# Schematic.net
KiCad netlist of a schematic drawn in Altium Designer
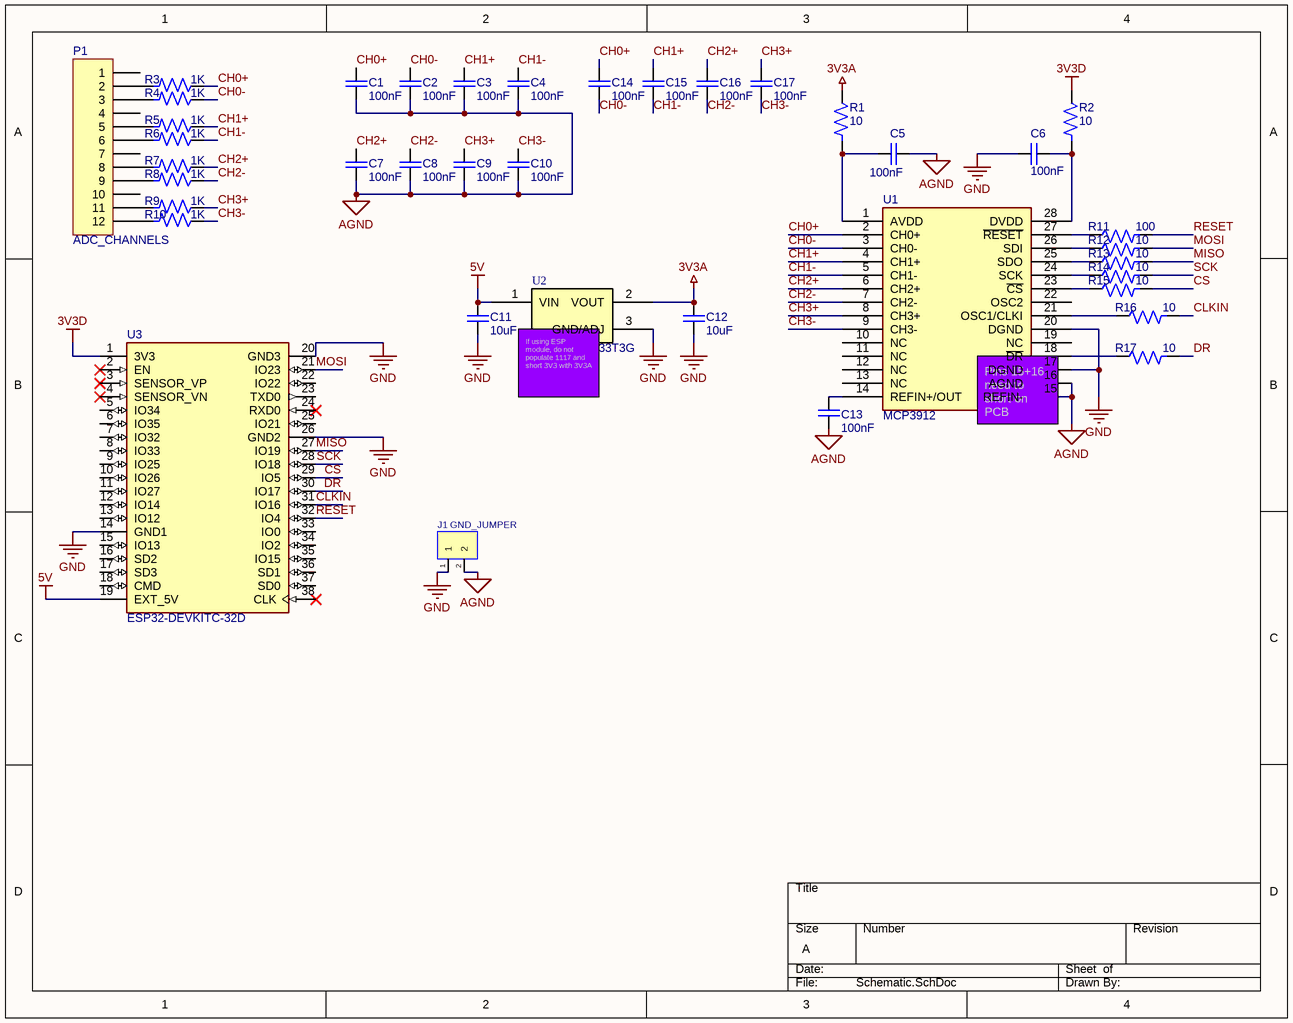
[diagram p0: Schematic.SchDoc]

(export (version "E")
  (design (tool "Eeschema 10.0.6"))
  (components
    (comp (ref "C1")
      (value "100nF")
      (footprint "CAP_0603")
      (description "Cap 100nF 6V 603 Ceramic")
      (fields
        (field (name "MANUFACTURER") "KEMET")
        (field (name "MANUFACTURER PART NUMBER") "C0603C104K9RACTU")
      )
      (libsource (lib "collection1") (part "Cap 100nF 6V 603 Ceramic"))
    )
    (comp (ref "C2")
      (value "100nF")
      (footprint "CAP_0603")
      (description "Cap 100nF 6V 603 Ceramic")
      (fields
        (field (name "MANUFACTURER") "KEMET")
        (field (name "MANUFACTURER PART NUMBER") "C0603C104K9RACTU")
      )
      (libsource (lib "collection1") (part "Cap 100nF 6V 603 Ceramic"))
    )
    (comp (ref "C3")
      (value "100nF")
      (footprint "CAP_0603")
      (description "Cap 100nF 6V 603 Ceramic")
      (fields
        (field (name "MANUFACTURER") "KEMET")
        (field (name "MANUFACTURER PART NUMBER") "C0603C104K9RACTU")
      )
      (libsource (lib "collection1") (part "Cap 100nF 6V 603 Ceramic"))
    )
    (comp (ref "C4")
      (value "100nF")
      (footprint "CAP_0603")
      (description "Cap 100nF 6V 603 Ceramic")
      (fields
        (field (name "MANUFACTURER") "KEMET")
        (field (name "MANUFACTURER PART NUMBER") "C0603C104K9RACTU")
      )
      (libsource (lib "collection1") (part "Cap 100nF 6V 603 Ceramic"))
    )
    (comp (ref "C5")
      (value "100nF")
      (footprint "CAP_0603")
      (description "Cap 100nF 6V 603 Ceramic")
      (fields
        (field (name "MANUFACTURER") "KEMET")
        (field (name "MANUFACTURER PART NUMBER") "C0603C104K9RACTU")
      )
      (libsource (lib "collection1") (part "Cap 100nF 6V 603 Ceramic"))
    )
    (comp (ref "C6")
      (value "100nF")
      (footprint "CAP_0603")
      (description "Cap 100nF 6V 603 Ceramic")
      (fields
        (field (name "MANUFACTURER") "KEMET")
        (field (name "MANUFACTURER PART NUMBER") "C0603C104K9RACTU")
      )
      (libsource (lib "collection1") (part "Cap 100nF 6V 603 Ceramic"))
    )
    (comp (ref "C7")
      (value "100nF")
      (footprint "CAP_0603")
      (description "Cap 100nF 6V 603 Ceramic")
      (fields
        (field (name "MANUFACTURER") "KEMET")
        (field (name "MANUFACTURER PART NUMBER") "C0603C104K9RACTU")
      )
      (libsource (lib "collection1") (part "Cap 100nF 6V 603 Ceramic"))
    )
    (comp (ref "C8")
      (value "100nF")
      (footprint "CAP_0603")
      (description "Cap 100nF 6V 603 Ceramic")
      (fields
        (field (name "MANUFACTURER") "KEMET")
        (field (name "MANUFACTURER PART NUMBER") "C0603C104K9RACTU")
      )
      (libsource (lib "collection1") (part "Cap 100nF 6V 603 Ceramic"))
    )
    (comp (ref "C9")
      (value "100nF")
      (footprint "CAP_0603")
      (description "Cap 100nF 6V 603 Ceramic")
      (fields
        (field (name "MANUFACTURER") "KEMET")
        (field (name "MANUFACTURER PART NUMBER") "C0603C104K9RACTU")
      )
      (libsource (lib "collection1") (part "Cap 100nF 6V 603 Ceramic"))
    )
    (comp (ref "C10")
      (value "100nF")
      (footprint "CAP_0603")
      (description "Cap 100nF 6V 603 Ceramic")
      (fields
        (field (name "MANUFACTURER") "KEMET")
        (field (name "MANUFACTURER PART NUMBER") "C0603C104K9RACTU")
      )
      (libsource (lib "collection1") (part "Cap 100nF 6V 603 Ceramic"))
    )
    (comp (ref "C11")
      (value "10uF")
      (footprint "CAP_0603")
      (description "Cap 100nF 6V 603 Ceramic")
      (fields
        (field (name "MANUFACTURER") "KEMET")
        (field (name "MANUFACTURER PART NUMBER") "C0603C104K9RACTU")
      )
      (libsource (lib "collection1") (part "Cap 100nF 6V 603 Ceramic"))
    )
    (comp (ref "C12")
      (value "10uF")
      (footprint "CAP_0603")
      (description "Cap 100nF 6V 603 Ceramic")
      (fields
        (field (name "MANUFACTURER") "KEMET")
        (field (name "MANUFACTURER PART NUMBER") "C0603C104K9RACTU")
      )
      (libsource (lib "collection1") (part "Cap 100nF 6V 603 Ceramic"))
    )
    (comp (ref "C13")
      (value "100nF")
      (footprint "CAP_0603")
      (description "Cap 100nF 6V 603 Ceramic")
      (fields
        (field (name "MANUFACTURER") "KEMET")
        (field (name "MANUFACTURER PART NUMBER") "C0603C104K9RACTU")
      )
      (libsource (lib "collection1") (part "Cap 100nF 6V 603 Ceramic"))
    )
    (comp (ref "C14")
      (value "100nF")
      (footprint "CAP_0603")
      (description "Cap 100nF 6V 603 Ceramic")
      (fields
        (field (name "MANUFACTURER") "KEMET")
        (field (name "MANUFACTURER PART NUMBER") "C0603C104K9RACTU")
      )
      (libsource (lib "collection1") (part "Cap 100nF 6V 603 Ceramic"))
    )
    (comp (ref "C15")
      (value "100nF")
      (footprint "CAP_0603")
      (description "Cap 100nF 6V 603 Ceramic")
      (fields
        (field (name "MANUFACTURER") "KEMET")
        (field (name "MANUFACTURER PART NUMBER") "C0603C104K9RACTU")
      )
      (libsource (lib "collection1") (part "Cap 100nF 6V 603 Ceramic"))
    )
    (comp (ref "C16")
      (value "100nF")
      (footprint "CAP_0603")
      (description "Cap 100nF 6V 603 Ceramic")
      (fields
        (field (name "MANUFACTURER") "KEMET")
        (field (name "MANUFACTURER PART NUMBER") "C0603C104K9RACTU")
      )
      (libsource (lib "collection1") (part "Cap 100nF 6V 603 Ceramic"))
    )
    (comp (ref "C17")
      (value "100nF")
      (footprint "CAP_0603")
      (description "Cap 100nF 6V 603 Ceramic")
      (fields
        (field (name "MANUFACTURER") "KEMET")
        (field (name "MANUFACTURER PART NUMBER") "C0603C104K9RACTU")
      )
      (libsource (lib "collection1") (part "Cap 100nF 6V 603 Ceramic"))
    )
    (comp (ref "J1")
      (value "GND_JUMPER")
      (footprint "CONN 2POS 2.54PITCH")
      (description "Connector Header Through Hole 2 position 0.100\" (2.54mm)")
      (fields (field (name "MANUFACTURER") "Molex") (field (name "MANUFACTURER PART NUMBER") "22-27-2021"))
      (libsource (lib "collection1") (part "CONN HEADER VERT 2POS 2.54MM"))
    )
    (comp (ref "P1")
      (value "ADC_CHANNELS")
      (footprint "HDR1X12")
      (description "Header, 12-Pin")
      (fields (field (name "PUBLISHER") "Altium Limited"))
      (libsource (lib "Miscellaneous Connectors") (part "Header 12"))
    )
    (comp (ref "R1")
      (value "10")
      (footprint "RES_0805")
      (description "Res 1K 0805 5% 1/8W")
      (fields
        (field (name "MANUFACTURER") "Yageo")
        (field (name "MANUFACTURER PART NUMBER") "RC0805JR-071KL")
      )
      (libsource (lib "collection1") (part "Res 1K 0805 5% 1/8W"))
    )
    (comp (ref "R2")
      (value "10")
      (footprint "RES_0805")
      (description "Res 1K 0805 5% 1/8W")
      (fields
        (field (name "MANUFACTURER") "Yageo")
        (field (name "MANUFACTURER PART NUMBER") "RC0805JR-071KL")
      )
      (libsource (lib "collection1") (part "Res 1K 0805 5% 1/8W"))
    )
    (comp (ref "R3")
      (value "1K")
      (footprint "RES_0805")
      (description "Res 1K 0805 5% 1/8W")
      (fields
        (field (name "MANUFACTURER") "Yageo")
        (field (name "MANUFACTURER PART NUMBER") "RC0805JR-071KL")
      )
      (libsource (lib "collection1") (part "Res 1K 0805 5% 1/8W"))
    )
    (comp (ref "R4")
      (value "1K")
      (footprint "RES_0805")
      (description "Res 1K 0805 5% 1/8W")
      (fields
        (field (name "MANUFACTURER") "Yageo")
        (field (name "MANUFACTURER PART NUMBER") "RC0805JR-071KL")
      )
      (libsource (lib "collection1") (part "Res 1K 0805 5% 1/8W"))
    )
    (comp (ref "R5")
      (value "1K")
      (footprint "RES_0805")
      (description "Res 1K 0805 5% 1/8W")
      (fields
        (field (name "MANUFACTURER") "Yageo")
        (field (name "MANUFACTURER PART NUMBER") "RC0805JR-071KL")
      )
      (libsource (lib "collection1") (part "Res 1K 0805 5% 1/8W"))
    )
    (comp (ref "R6")
      (value "1K")
      (footprint "RES_0805")
      (description "Res 1K 0805 5% 1/8W")
      (fields
        (field (name "MANUFACTURER") "Yageo")
        (field (name "MANUFACTURER PART NUMBER") "RC0805JR-071KL")
      )
      (libsource (lib "collection1") (part "Res 1K 0805 5% 1/8W"))
    )
    (comp (ref "R7")
      (value "1K")
      (footprint "RES_0805")
      (description "Res 1K 0805 5% 1/8W")
      (fields
        (field (name "MANUFACTURER") "Yageo")
        (field (name "MANUFACTURER PART NUMBER") "RC0805JR-071KL")
      )
      (libsource (lib "collection1") (part "Res 1K 0805 5% 1/8W"))
    )
    (comp (ref "R8")
      (value "1K")
      (footprint "RES_0805")
      (description "Res 1K 0805 5% 1/8W")
      (fields
        (field (name "MANUFACTURER") "Yageo")
        (field (name "MANUFACTURER PART NUMBER") "RC0805JR-071KL")
      )
      (libsource (lib "collection1") (part "Res 1K 0805 5% 1/8W"))
    )
    (comp (ref "R9")
      (value "1K")
      (footprint "RES_0805")
      (description "Res 1K 0805 5% 1/8W")
      (fields
        (field (name "MANUFACTURER") "Yageo")
        (field (name "MANUFACTURER PART NUMBER") "RC0805JR-071KL")
      )
      (libsource (lib "collection1") (part "Res 1K 0805 5% 1/8W"))
    )
    (comp (ref "R10")
      (value "1K")
      (footprint "RES_0805")
      (description "Res 1K 0805 5% 1/8W")
      (fields
        (field (name "MANUFACTURER") "Yageo")
        (field (name "MANUFACTURER PART NUMBER") "RC0805JR-071KL")
      )
      (libsource (lib "collection1") (part "Res 1K 0805 5% 1/8W"))
    )
    (comp (ref "R11")
      (value "100")
      (footprint "RES_0805")
      (description "Res 1K 0805 5% 1/8W")
      (fields
        (field (name "MANUFACTURER") "Yageo")
        (field (name "MANUFACTURER PART NUMBER") "RC0805JR-071KL")
      )
      (libsource (lib "collection1") (part "Res 1K 0805 5% 1/8W"))
    )
    (comp (ref "R12")
      (value "10")
      (footprint "RES_0805")
      (description "Res 1K 0805 5% 1/8W")
      (fields
        (field (name "MANUFACTURER") "Yageo")
        (field (name "MANUFACTURER PART NUMBER") "RC0805JR-071KL")
      )
      (libsource (lib "collection1") (part "Res 1K 0805 5% 1/8W"))
    )
    (comp (ref "R13")
      (value "10")
      (footprint "RES_0805")
      (description "Res 1K 0805 5% 1/8W")
      (fields
        (field (name "MANUFACTURER") "Yageo")
        (field (name "MANUFACTURER PART NUMBER") "RC0805JR-071KL")
      )
      (libsource (lib "collection1") (part "Res 1K 0805 5% 1/8W"))
    )
    (comp (ref "R14")
      (value "10")
      (footprint "RES_0805")
      (description "Res 1K 0805 5% 1/8W")
      (fields
        (field (name "MANUFACTURER") "Yageo")
        (field (name "MANUFACTURER PART NUMBER") "RC0805JR-071KL")
      )
      (libsource (lib "collection1") (part "Res 1K 0805 5% 1/8W"))
    )
    (comp (ref "R15")
      (value "10")
      (footprint "RES_0805")
      (description "Res 1K 0805 5% 1/8W")
      (fields
        (field (name "MANUFACTURER") "Yageo")
        (field (name "MANUFACTURER PART NUMBER") "RC0805JR-071KL")
      )
      (libsource (lib "collection1") (part "Res 1K 0805 5% 1/8W"))
    )
    (comp (ref "R16")
      (value "10")
      (footprint "RES_0805")
      (description "Res 1K 0805 5% 1/8W")
      (fields
        (field (name "MANUFACTURER") "Yageo")
        (field (name "MANUFACTURER PART NUMBER") "RC0805JR-071KL")
      )
      (libsource (lib "collection1") (part "Res 1K 0805 5% 1/8W"))
    )
    (comp (ref "R17")
      (value "10")
      (footprint "RES_0805")
      (description "Res 1K 0805 5% 1/8W")
      (fields
        (field (name "MANUFACTURER") "Yageo")
        (field (name "MANUFACTURER PART NUMBER") "RC0805JR-071KL")
      )
      (libsource (lib "collection1") (part "Res 1K 0805 5% 1/8W"))
    )
    (comp (ref "U1")
      (value "MCP3912")
      (footprint "TI SSOP-24 DB")
      (libsource (lib "bio_components") (part "MCP3912"))
    )
    (comp (ref "U2")
      (value "NCP1117ST33T3G")
      (footprint "SOT223")
      (libsource (lib "ch340C") (part "NCP1117ST33T3G"))
    )
    (comp (ref "U3")
      (value "ESP32-DEVKITC-32D")
      (footprint "MODULE_ESP32-DEVKITC-32D:MODULE_ESP32-DEVKITC-32D")
      (description "EVAL BOARD FOR ESP-WROOM-32")
      (fields (field (name "MF") "Espressif Systems"))
      (libsource (lib "bio_components") (part "ESP32-DEVKITC-32D"))
    )
  )
  (nets
    (net (code "1") (name "/CH0+") (class "Default")
      (node (ref "C1") (pin "1") (pinfunction "1_1") (pintype "passive"))
      (node (ref "C14") (pin "1") (pinfunction "1_1") (pintype "passive"))
      (node (ref "R3") (pin "2") (pinfunction "2_2") (pintype "passive"))
      (node (ref "U1") (pin "2") (pinfunction "CH0+_2") (pintype "passive"))
    )
    (net (code "2") (name "/CH0-") (class "Default")
      (node (ref "C14") (pin "2") (pinfunction "2_2") (pintype "passive"))
      (node (ref "C2") (pin "1") (pinfunction "1_1") (pintype "passive"))
      (node (ref "R4") (pin "2") (pinfunction "2_2") (pintype "passive"))
      (node (ref "U1") (pin "3") (pinfunction "CH0-_3") (pintype "passive"))
    )
    (net (code "3") (name "/CH1+") (class "Default")
      (node (ref "C15") (pin "1") (pinfunction "1_1") (pintype "passive"))
      (node (ref "C3") (pin "1") (pinfunction "1_1") (pintype "passive"))
      (node (ref "R5") (pin "2") (pinfunction "2_2") (pintype "passive"))
      (node (ref "U1") (pin "4") (pinfunction "CH1+_4") (pintype "passive"))
    )
    (net (code "4") (name "/CH1-") (class "Default")
      (node (ref "C15") (pin "2") (pinfunction "2_2") (pintype "passive"))
      (node (ref "C4") (pin "1") (pinfunction "1_1") (pintype "passive"))
      (node (ref "R6") (pin "2") (pinfunction "2_2") (pintype "passive"))
      (node (ref "U1") (pin "5") (pinfunction "CH1-_5") (pintype "passive"))
    )
    (net (code "5") (name "/CH2+") (class "Default")
      (node (ref "C16") (pin "1") (pinfunction "1_1") (pintype "passive"))
      (node (ref "C7") (pin "1") (pinfunction "1_1") (pintype "passive"))
      (node (ref "R7") (pin "2") (pinfunction "2_2") (pintype "passive"))
      (node (ref "U1") (pin "6") (pinfunction "CH2+_6") (pintype "passive"))
    )
    (net (code "6") (name "/CH2-") (class "Default")
      (node (ref "C16") (pin "2") (pinfunction "2_2") (pintype "passive"))
      (node (ref "C8") (pin "1") (pinfunction "1_1") (pintype "passive"))
      (node (ref "R8") (pin "2") (pinfunction "2_2") (pintype "passive"))
      (node (ref "U1") (pin "7") (pinfunction "CH2-_7") (pintype "passive"))
    )
    (net (code "7") (name "/CH3+") (class "Default")
      (node (ref "C17") (pin "1") (pinfunction "1_1") (pintype "passive"))
      (node (ref "C9") (pin "1") (pinfunction "1_1") (pintype "passive"))
      (node (ref "R9") (pin "2") (pinfunction "2_2") (pintype "passive"))
      (node (ref "U1") (pin "8") (pinfunction "CH3+_8") (pintype "passive"))
    )
    (net (code "8") (name "/CH3-") (class "Default")
      (node (ref "C10") (pin "1") (pinfunction "1_1") (pintype "passive"))
      (node (ref "C17") (pin "2") (pinfunction "2_2") (pintype "passive"))
      (node (ref "R10") (pin "2") (pinfunction "2_2") (pintype "passive"))
      (node (ref "U1") (pin "9") (pinfunction "CH3-_9") (pintype "passive"))
    )
    (net (code "9") (name "/CLKIN") (class "Default")
      (node (ref "R16") (pin "1") (pinfunction "1_1") (pintype "passive"))
      (node (ref "U3") (pin "31") (pinfunction "IO16_31") (pintype "bidirectional"))
    )
    (net (code "10") (name "/CS") (class "Default")
      (node (ref "R15") (pin "1") (pinfunction "1_1") (pintype "passive"))
      (node (ref "U3") (pin "29") (pinfunction "IO5_29") (pintype "bidirectional"))
    )
    (net (code "11") (name "/DR") (class "Default")
      (node (ref "R17") (pin "1") (pinfunction "1_1") (pintype "passive"))
      (node (ref "U3") (pin "30") (pinfunction "IO17_30") (pintype "bidirectional"))
    )
    (net (code "12") (name "/MISO") (class "Default")
      (node (ref "R13") (pin "1") (pinfunction "1_1") (pintype "passive"))
      (node (ref "U3") (pin "27") (pinfunction "IO19_27") (pintype "bidirectional"))
    )
    (net (code "13") (name "/MOSI") (class "Default")
      (node (ref "R12") (pin "1") (pinfunction "1_1") (pintype "passive"))
      (node (ref "U3") (pin "21") (pinfunction "IO23_21") (pintype "bidirectional"))
    )
    (net (code "14") (name "/RESET") (class "Default")
      (node (ref "R11") (pin "1") (pinfunction "1_1") (pintype "passive"))
      (node (ref "U3") (pin "32") (pinfunction "IO4_32") (pintype "bidirectional"))
    )
    (net (code "15") (name "/SCK") (class "Default")
      (node (ref "R14") (pin "1") (pinfunction "1_1") (pintype "passive"))
      (node (ref "U3") (pin "28") (pinfunction "IO18_28") (pintype "bidirectional"))
    )
    (net (code "16") (name "3V3A") (class "Default")
      (node (ref "C12") (pin "1") (pinfunction "1_1") (pintype "passive"))
      (node (ref "R1") (pin "2") (pinfunction "2_2") (pintype "passive"))
      (node (ref "U2") (pin "2") (pinfunction "VOUT_2") (pintype "passive"))
    )
    (net (code "17") (name "3V3D") (class "Default")
      (node (ref "R2") (pin "2") (pinfunction "2_2") (pintype "passive"))
      (node (ref "U3") (pin "1") (pinfunction "3V3_1") (pintype "power_in"))
    )
    (net (code "18") (name "5V") (class "Default")
      (node (ref "C11") (pin "1") (pinfunction "1_1") (pintype "passive"))
      (node (ref "U2") (pin "1") (pinfunction "VIN_1") (pintype "passive"))
      (node (ref "U3") (pin "19") (pinfunction "EXT_5V_19") (pintype "power_in"))
    )
    (net (code "19") (name "AGND") (class "Default")
      (node (ref "C1") (pin "2") (pinfunction "2_2") (pintype "passive"))
      (node (ref "C10") (pin "2") (pinfunction "2_2") (pintype "passive"))
      (node (ref "C13") (pin "1") (pinfunction "1_1") (pintype "passive"))
      (node (ref "C2") (pin "2") (pinfunction "2_2") (pintype "passive"))
      (node (ref "C3") (pin "2") (pinfunction "2_2") (pintype "passive"))
      (node (ref "C4") (pin "2") (pinfunction "2_2") (pintype "passive"))
      (node (ref "C5") (pin "2") (pinfunction "2_2") (pintype "passive"))
      (node (ref "C7") (pin "2") (pinfunction "2_2") (pintype "passive"))
      (node (ref "C8") (pin "2") (pinfunction "2_2") (pintype "passive"))
      (node (ref "C9") (pin "2") (pinfunction "2_2") (pintype "passive"))
      (node (ref "J1") (pin "2") (pinfunction "2_2") (pintype "passive"))
      (node (ref "U1") (pin "15") (pinfunction "REFIN-_15") (pintype "passive"))
      (node (ref "U1") (pin "16") (pinfunction "AGND_16") (pintype "passive"))
    )
    (net (code "20") (name "GND") (class "Default")
      (node (ref "C11") (pin "2") (pinfunction "2_2") (pintype "passive"))
      (node (ref "C12") (pin "2") (pinfunction "2_2") (pintype "passive"))
      (node (ref "C6") (pin "1") (pinfunction "1_1") (pintype "passive"))
      (node (ref "J1") (pin "1") (pinfunction "1_1") (pintype "passive"))
      (node (ref "U1") (pin "17") (pinfunction "DGND_17") (pintype "passive"))
      (node (ref "U1") (pin "20") (pinfunction "DGND_20") (pintype "passive"))
      (node (ref "U2") (pin "3") (pinfunction "GND/ADJ_3") (pintype "passive"))
      (node (ref "U3") (pin "14") (pinfunction "GND1_14") (pintype "power_in"))
      (node (ref "U3") (pin "20") (pinfunction "GND3_20") (pintype "power_in"))
      (node (ref "U3") (pin "26") (pinfunction "GND2_26") (pintype "power_in"))
    )
    (net (code "21") (name "Net-(P1-Pad2)") (class "Default")
      (node (ref "P1") (pin "2") (pinfunction "2_2") (pintype "passive"))
      (node (ref "R3") (pin "1") (pinfunction "1_1") (pintype "passive"))
    )
    (net (code "22") (name "Net-(P1-Pad3)") (class "Default")
      (node (ref "P1") (pin "3") (pinfunction "3_3") (pintype "passive"))
      (node (ref "R4") (pin "1") (pinfunction "1_1") (pintype "passive"))
    )
    (net (code "23") (name "Net-(P1-Pad5)") (class "Default")
      (node (ref "P1") (pin "5") (pinfunction "5_5") (pintype "passive"))
      (node (ref "R5") (pin "1") (pinfunction "1_1") (pintype "passive"))
    )
    (net (code "24") (name "Net-(P1-Pad6)") (class "Default")
      (node (ref "P1") (pin "6") (pinfunction "6_6") (pintype "passive"))
      (node (ref "R6") (pin "1") (pinfunction "1_1") (pintype "passive"))
    )
    (net (code "25") (name "Net-(P1-Pad8)") (class "Default")
      (node (ref "P1") (pin "8") (pinfunction "8_8") (pintype "passive"))
      (node (ref "R7") (pin "1") (pinfunction "1_1") (pintype "passive"))
    )
    (net (code "26") (name "Net-(P1-Pad9)") (class "Default")
      (node (ref "P1") (pin "9") (pinfunction "9_9") (pintype "passive"))
      (node (ref "R8") (pin "1") (pinfunction "1_1") (pintype "passive"))
    )
    (net (code "27") (name "Net-(P1-Pad11)") (class "Default")
      (node (ref "P1") (pin "11") (pinfunction "11_11") (pintype "passive"))
      (node (ref "R9") (pin "1") (pinfunction "1_1") (pintype "passive"))
    )
    (net (code "28") (name "Net-(P1-Pad12)") (class "Default")
      (node (ref "P1") (pin "12") (pinfunction "12_12") (pintype "passive"))
      (node (ref "R10") (pin "1") (pinfunction "1_1") (pintype "passive"))
    )
    (net (code "29") (name "Net-(U1-AVDD)") (class "Default")
      (node (ref "C5") (pin "1") (pinfunction "1_1") (pintype "passive"))
      (node (ref "R1") (pin "1") (pinfunction "1_1") (pintype "passive"))
      (node (ref "U1") (pin "1") (pinfunction "AVDD_1") (pintype "passive"))
    )
    (net (code "30") (name "Net-(U1-DVDD)") (class "Default")
      (node (ref "C6") (pin "2") (pinfunction "2_2") (pintype "passive"))
      (node (ref "R2") (pin "1") (pinfunction "1_1") (pintype "passive"))
      (node (ref "U1") (pin "28") (pinfunction "DVDD_28") (pintype "passive"))
    )
    (net (code "31") (name "Net-(U1-OSC1{slash}CLKI)") (class "Default")
      (node (ref "R16") (pin "2") (pinfunction "2_2") (pintype "passive"))
      (node (ref "U1") (pin "21") (pinfunction "OSC1/CLKI_21") (pintype "passive"))
    )
    (net (code "32") (name "Net-(U1-REFIN+{slash}OUT)") (class "Default")
      (node (ref "C13") (pin "2") (pinfunction "2_2") (pintype "passive"))
      (node (ref "U1") (pin "14") (pinfunction "REFIN+/OUT_14") (pintype "passive"))
    )
    (net (code "33") (name "Net-(U1-SCK)") (class "Default")
      (node (ref "R14") (pin "2") (pinfunction "2_2") (pintype "passive"))
      (node (ref "U1") (pin "24") (pinfunction "SCK_24") (pintype "passive"))
    )
    (net (code "34") (name "Net-(U1-SDI)") (class "Default")
      (node (ref "R12") (pin "2") (pinfunction "2_2") (pintype "passive"))
      (node (ref "U1") (pin "26") (pinfunction "SDI_26") (pintype "passive"))
    )
    (net (code "35") (name "Net-(U1-SDO)") (class "Default")
      (node (ref "R13") (pin "2") (pinfunction "2_2") (pintype "passive"))
      (node (ref "U1") (pin "25") (pinfunction "SDO_25") (pintype "passive"))
    )
    (net (code "36") (name "Net-(U1-~{CS})") (class "Default")
      (node (ref "R15") (pin "2") (pinfunction "2_2") (pintype "passive"))
      (node (ref "U1") (pin "23") (pinfunction "~{CS}_23") (pintype "passive"))
    )
    (net (code "37") (name "Net-(U1-~{DR})") (class "Default")
      (node (ref "R17") (pin "2") (pinfunction "2_2") (pintype "passive"))
      (node (ref "U1") (pin "18") (pinfunction "~{DR}_18") (pintype "passive"))
    )
    (net (code "38") (name "Net-(U1-~{RESET})") (class "Default")
      (node (ref "R11") (pin "2") (pinfunction "2_2") (pintype "passive"))
      (node (ref "U1") (pin "27") (pinfunction "~{RESET}_27") (pintype "passive"))
    )
    (net (code "39") (name "unconnected-(P1-Pad1)") (class "Default")
      (node (ref "P1") (pin "1") (pinfunction "1_1") (pintype "passive"))
    )
    (net (code "40") (name "unconnected-(P1-Pad4)") (class "Default")
      (node (ref "P1") (pin "4") (pinfunction "4_4") (pintype "passive"))
    )
    (net (code "41") (name "unconnected-(P1-Pad7)") (class "Default")
      (node (ref "P1") (pin "7") (pinfunction "7_7") (pintype "passive"))
    )
    (net (code "42") (name "unconnected-(P1-Pad10)") (class "Default")
      (node (ref "P1") (pin "10") (pinfunction "10_10") (pintype "passive"))
    )
    (net (code "43") (name "unconnected-(U1-NC-Pad10)") (class "Default")
      (node (ref "U1") (pin "10") (pinfunction "NC_10") (pintype "passive"))
    )
    (net (code "44") (name "unconnected-(U1-NC-Pad11)") (class "Default")
      (node (ref "U1") (pin "11") (pinfunction "NC_11") (pintype "passive"))
    )
    (net (code "45") (name "unconnected-(U1-NC-Pad12)") (class "Default")
      (node (ref "U1") (pin "12") (pinfunction "NC_12") (pintype "passive"))
    )
    (net (code "46") (name "unconnected-(U1-NC-Pad13)") (class "Default")
      (node (ref "U1") (pin "13") (pinfunction "NC_13") (pintype "passive"))
    )
    (net (code "47") (name "unconnected-(U1-NC-Pad19)") (class "Default")
      (node (ref "U1") (pin "19") (pinfunction "NC_19") (pintype "passive"))
    )
    (net (code "48") (name "unconnected-(U1-OSC2-Pad22)") (class "Default")
      (node (ref "U1") (pin "22") (pinfunction "OSC2_22") (pintype "passive"))
    )
    (net (code "49") (name "unconnected-(U3-CLK-Pad38)") (class "Default")
      (node (ref "U3") (pin "38") (pinfunction "CLK_38") (pintype "input+no_connect"))
    )
    (net (code "50") (name "unconnected-(U3-CMD-Pad18)") (class "Default")
      (node (ref "U3") (pin "18") (pinfunction "CMD_18") (pintype "bidirectional"))
    )
    (net (code "51") (name "unconnected-(U3-EN-Pad2)") (class "Default")
      (node (ref "U3") (pin "2") (pinfunction "EN_2") (pintype "input+no_connect"))
    )
    (net (code "52") (name "unconnected-(U3-IO0-Pad33)") (class "Default")
      (node (ref "U3") (pin "33") (pinfunction "IO0_33") (pintype "bidirectional"))
    )
    (net (code "53") (name "unconnected-(U3-IO2-Pad34)") (class "Default")
      (node (ref "U3") (pin "34") (pinfunction "IO2_34") (pintype "bidirectional"))
    )
    (net (code "54") (name "unconnected-(U3-IO12-Pad13)") (class "Default")
      (node (ref "U3") (pin "13") (pinfunction "IO12_13") (pintype "bidirectional"))
    )
    (net (code "55") (name "unconnected-(U3-IO13-Pad15)") (class "Default")
      (node (ref "U3") (pin "15") (pinfunction "IO13_15") (pintype "bidirectional"))
    )
    (net (code "56") (name "unconnected-(U3-IO14-Pad12)") (class "Default")
      (node (ref "U3") (pin "12") (pinfunction "IO14_12") (pintype "bidirectional"))
    )
    (net (code "57") (name "unconnected-(U3-IO15-Pad35)") (class "Default")
      (node (ref "U3") (pin "35") (pinfunction "IO15_35") (pintype "bidirectional"))
    )
    (net (code "58") (name "unconnected-(U3-IO21-Pad25)") (class "Default")
      (node (ref "U3") (pin "25") (pinfunction "IO21_25") (pintype "bidirectional"))
    )
    (net (code "59") (name "unconnected-(U3-IO22-Pad22)") (class "Default")
      (node (ref "U3") (pin "22") (pinfunction "IO22_22") (pintype "bidirectional"))
    )
    (net (code "60") (name "unconnected-(U3-IO25-Pad9)") (class "Default")
      (node (ref "U3") (pin "9") (pinfunction "IO25_9") (pintype "bidirectional"))
    )
    (net (code "61") (name "unconnected-(U3-IO26-Pad10)") (class "Default")
      (node (ref "U3") (pin "10") (pinfunction "IO26_10") (pintype "bidirectional"))
    )
    (net (code "62") (name "unconnected-(U3-IO27-Pad11)") (class "Default")
      (node (ref "U3") (pin "11") (pinfunction "IO27_11") (pintype "bidirectional"))
    )
    (net (code "63") (name "unconnected-(U3-IO32-Pad7)") (class "Default")
      (node (ref "U3") (pin "7") (pinfunction "IO32_7") (pintype "bidirectional"))
    )
    (net (code "64") (name "unconnected-(U3-IO33-Pad8)") (class "Default")
      (node (ref "U3") (pin "8") (pinfunction "IO33_8") (pintype "bidirectional"))
    )
    (net (code "65") (name "unconnected-(U3-IO34-Pad5)") (class "Default")
      (node (ref "U3") (pin "5") (pinfunction "IO34_5") (pintype "bidirectional"))
    )
    (net (code "66") (name "unconnected-(U3-IO35-Pad6)") (class "Default")
      (node (ref "U3") (pin "6") (pinfunction "IO35_6") (pintype "bidirectional"))
    )
    (net (code "67") (name "unconnected-(U3-RXD0-Pad24)") (class "Default")
      (node (ref "U3") (pin "24") (pinfunction "RXD0_24") (pintype "input+no_connect"))
    )
    (net (code "68") (name "unconnected-(U3-SD0-Pad37)") (class "Default")
      (node (ref "U3") (pin "37") (pinfunction "SD0_37") (pintype "bidirectional"))
    )
    (net (code "69") (name "unconnected-(U3-SD1-Pad36)") (class "Default")
      (node (ref "U3") (pin "36") (pinfunction "SD1_36") (pintype "bidirectional"))
    )
    (net (code "70") (name "unconnected-(U3-SD2-Pad16)") (class "Default")
      (node (ref "U3") (pin "16") (pinfunction "SD2_16") (pintype "bidirectional"))
    )
    (net (code "71") (name "unconnected-(U3-SD3-Pad17)") (class "Default")
      (node (ref "U3") (pin "17") (pinfunction "SD3_17") (pintype "bidirectional"))
    )
    (net (code "72") (name "unconnected-(U3-SENSOR_VN-Pad4)") (class "Default")
      (node (ref "U3") (pin "4") (pinfunction "SENSOR_VN_4") (pintype "input+no_connect"))
    )
    (net (code "73") (name "unconnected-(U3-SENSOR_VP-Pad3)") (class "Default")
      (node (ref "U3") (pin "3") (pinfunction "SENSOR_VP_3") (pintype "input+no_connect"))
    )
    (net (code "74") (name "unconnected-(U3-TXD0-Pad23)") (class "Default")
      (node (ref "U3") (pin "23") (pinfunction "TXD0_23") (pintype "output"))
    )
  )
)
